# HEATER.net
KiCad netlist of a schematic drawn in Altium Designer
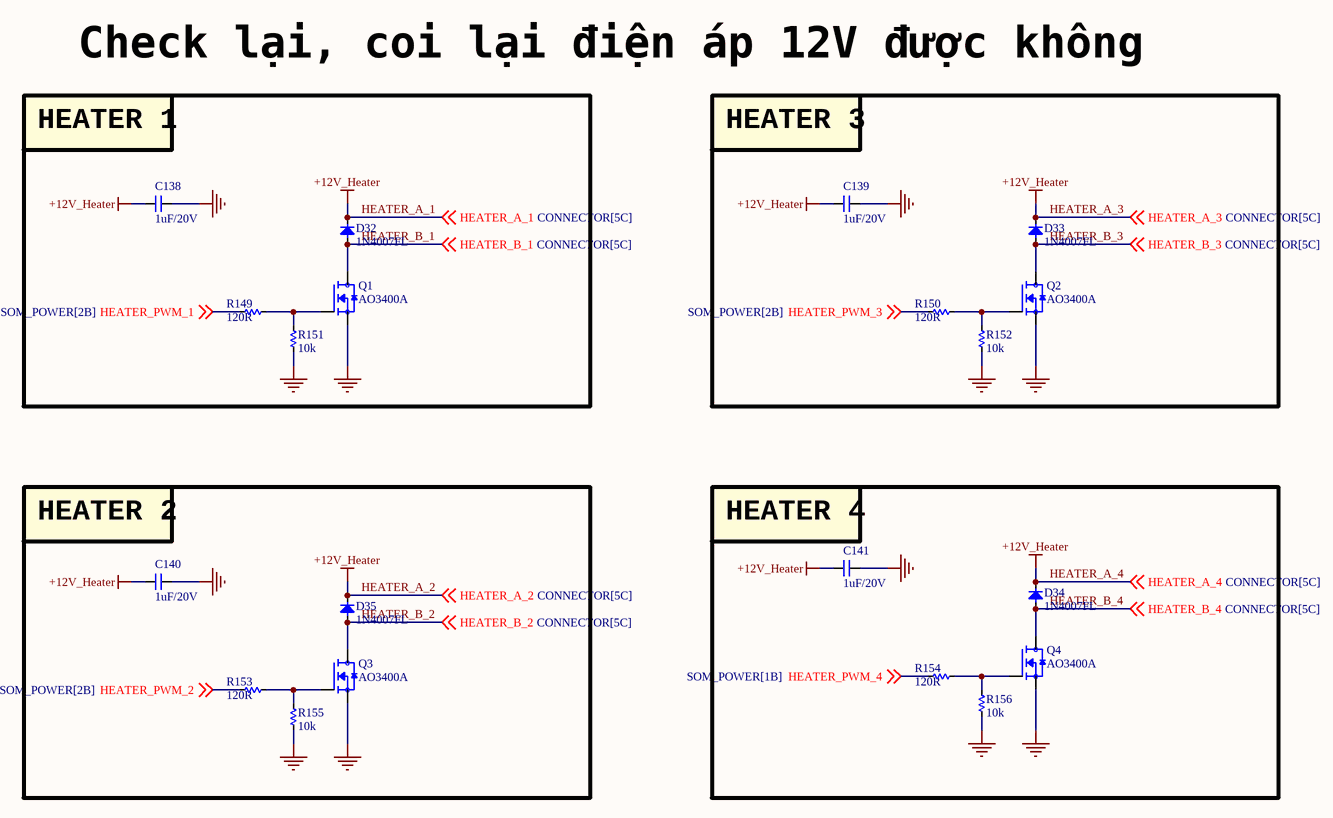
[diagram p0: HEATER.SchDoc]

(export (version "E")
  (design (tool "Eeschema 10.0.6"))
  (components
    (comp (ref "C138")
      (value "1uF/20V")
      (footprint "CAP_C_1005X60")
      (description "CAP CHIP")
      (libsource (lib "LABLIB") (part "_CAP_C_2"))
    )
    (comp (ref "C139")
      (value "1uF/20V")
      (footprint "CAP_C_1005X60")
      (description "CAP CHIP")
      (libsource (lib "LABLIB") (part "_CAP_C_2"))
    )
    (comp (ref "C140")
      (value "1uF/20V")
      (footprint "CAP_C_1005X60")
      (description "CAP CHIP")
      (libsource (lib "LABLIB") (part "_CAP_C_2"))
    )
    (comp (ref "C141")
      (value "1uF/20V")
      (footprint "CAP_C_1005X60")
      (description "CAP CHIP")
      (libsource (lib "LABLIB") (part "_CAP_C_2"))
    )
    (comp (ref "D32")
      (value "1N4007FL")
      (footprint "DIO-SMD-106")
      (description "Default Diode")
      (fields (field (name "PUBLISHER") "Altium Limited"))
      (libsource (lib "LABLIB") (part "Diode SMD"))
    )
    (comp (ref "D33")
      (value "1N4007FL")
      (footprint "DIO-SMD-106")
      (description "Default Diode")
      (fields (field (name "PUBLISHER") "Altium Limited"))
      (libsource (lib "LABLIB") (part "Diode SMD"))
    )
    (comp (ref "D34")
      (value "1N4007FL")
      (footprint "DIO-SMD-106")
      (description "Default Diode")
      (fields (field (name "PUBLISHER") "Altium Limited"))
      (libsource (lib "LABLIB") (part "Diode SMD"))
    )
    (comp (ref "D35")
      (value "1N4007FL")
      (footprint "DIO-SMD-106")
      (description "Default Diode")
      (fields (field (name "PUBLISHER") "Altium Limited"))
      (libsource (lib "LABLIB") (part "Diode SMD"))
    )
    (comp (ref "Q1")
      (value "AO3400A")
      (footprint "SOT95P240X120-3N")
      (description "N-Channel 30 V 5.7A (Ta) 1.4W (Ta) Surface Mount SOT-23-3")
      (fields (field (name "MF") "Alpha & Omega Semiconductor"))
      (libsource (lib "new_component") (part "MOSFET_N"))
    )
    (comp (ref "Q2")
      (value "AO3400A")
      (footprint "SOT95P240X120-3N")
      (description "N-Channel 30 V 5.7A (Ta) 1.4W (Ta) Surface Mount SOT-23-3")
      (fields (field (name "MF") "Alpha & Omega Semiconductor"))
      (libsource (lib "new_component") (part "MOSFET_N"))
    )
    (comp (ref "Q3")
      (value "AO3400A")
      (footprint "SOT95P240X120-3N")
      (description "N-Channel 30 V 5.7A (Ta) 1.4W (Ta) Surface Mount SOT-23-3")
      (fields (field (name "MF") "Alpha & Omega Semiconductor"))
      (libsource (lib "new_component") (part "MOSFET_N"))
    )
    (comp (ref "Q4")
      (value "AO3400A")
      (footprint "SOT95P240X120-3N")
      (description "N-Channel 30 V 5.7A (Ta) 1.4W (Ta) Surface Mount SOT-23-3")
      (fields (field (name "MF") "Alpha & Omega Semiconductor"))
      (libsource (lib "new_component") (part "MOSFET_N"))
    )
    (comp (ref "R149")
      (value "120R")
      (footprint "RES_C_1005X40")
      (description "RES")
      (libsource (lib "LABLIB") (part "_RES_B_2"))
    )
    (comp (ref "R150")
      (value "120R")
      (footprint "RES_C_1005X40")
      (description "RES")
      (libsource (lib "LABLIB") (part "_RES_B_2"))
    )
    (comp (ref "R151")
      (value "10k")
      (footprint "RES_C_1005X40")
      (description "RES")
      (libsource (lib "LABLIB") (part "_RES_B_2"))
    )
    (comp (ref "R152")
      (value "10k")
      (footprint "RES_C_1005X40")
      (description "RES")
      (libsource (lib "LABLIB") (part "_RES_B_2"))
    )
    (comp (ref "R153")
      (value "120R")
      (footprint "RES_C_1005X40")
      (description "RES")
      (libsource (lib "LABLIB") (part "_RES_B_2"))
    )
    (comp (ref "R154")
      (value "120R")
      (footprint "RES_C_1005X40")
      (description "RES")
      (libsource (lib "LABLIB") (part "_RES_B_2"))
    )
    (comp (ref "R155")
      (value "10k")
      (footprint "RES_C_1005X40")
      (description "RES")
      (libsource (lib "LABLIB") (part "_RES_B_2"))
    )
    (comp (ref "R156")
      (value "10k")
      (footprint "RES_C_1005X40")
      (description "RES")
      (libsource (lib "LABLIB") (part "_RES_B_2"))
    )
  )
  (nets
    (net (code "1") (name "+12V_Heater") (class "Default")
      (node (ref "C138") (pin "2") (pinfunction "2_2") (pintype "passive"))
      (node (ref "C139") (pin "2") (pinfunction "2_2") (pintype "passive"))
      (node (ref "C140") (pin "2") (pinfunction "2_2") (pintype "passive"))
      (node (ref "C141") (pin "2") (pinfunction "2_2") (pintype "passive"))
      (node (ref "D32") (pin "1") (pinfunction "K_1") (pintype "passive"))
      (node (ref "D33") (pin "1") (pinfunction "K_1") (pintype "passive"))
      (node (ref "D34") (pin "1") (pinfunction "K_1") (pintype "passive"))
      (node (ref "D35") (pin "1") (pinfunction "K_1") (pintype "passive"))
    )
    (net (code "2") (name "GND") (class "Default")
      (node (ref "C138") (pin "1") (pinfunction "1_1") (pintype "passive"))
      (node (ref "C139") (pin "1") (pinfunction "1_1") (pintype "passive"))
      (node (ref "C140") (pin "1") (pinfunction "1_1") (pintype "passive"))
      (node (ref "C141") (pin "1") (pinfunction "1_1") (pintype "passive"))
      (node (ref "Q1") (pin "2") (pinfunction "S_2") (pintype "passive"))
      (node (ref "Q2") (pin "2") (pinfunction "S_2") (pintype "passive"))
      (node (ref "Q3") (pin "2") (pinfunction "S_2") (pintype "passive"))
      (node (ref "Q4") (pin "2") (pinfunction "S_2") (pintype "passive"))
      (node (ref "R151") (pin "1") (pinfunction "1_1") (pintype "passive"))
      (node (ref "R152") (pin "1") (pinfunction "1_1") (pintype "passive"))
      (node (ref "R155") (pin "1") (pinfunction "1_1") (pintype "passive"))
      (node (ref "R156") (pin "1") (pinfunction "1_1") (pintype "passive"))
    )
    (net (code "3") (name "HEATER_B_1") (class "Default")
      (node (ref "D32") (pin "2") (pinfunction "A_2") (pintype "passive"))
      (node (ref "Q1") (pin "3") (pinfunction "D_3") (pintype "passive"))
    )
    (net (code "4") (name "HEATER_B_2") (class "Default")
      (node (ref "D35") (pin "2") (pinfunction "A_2") (pintype "passive"))
      (node (ref "Q3") (pin "3") (pinfunction "D_3") (pintype "passive"))
    )
    (net (code "5") (name "HEATER_B_3") (class "Default")
      (node (ref "D33") (pin "2") (pinfunction "A_2") (pintype "passive"))
      (node (ref "Q2") (pin "3") (pinfunction "D_3") (pintype "passive"))
    )
    (net (code "6") (name "HEATER_B_4") (class "Default")
      (node (ref "D34") (pin "2") (pinfunction "A_2") (pintype "passive"))
      (node (ref "Q4") (pin "3") (pinfunction "D_3") (pintype "passive"))
    )
    (net (code "7") (name "HEATER_PWM_1") (class "Default")
      (node (ref "R149") (pin "1") (pinfunction "1_1") (pintype "passive"))
    )
    (net (code "8") (name "HEATER_PWM_2") (class "Default")
      (node (ref "R153") (pin "1") (pinfunction "1_1") (pintype "passive"))
    )
    (net (code "9") (name "HEATER_PWM_3") (class "Default")
      (node (ref "R150") (pin "1") (pinfunction "1_1") (pintype "passive"))
    )
    (net (code "10") (name "HEATER_PWM_4") (class "Default")
      (node (ref "R154") (pin "1") (pinfunction "1_1") (pintype "passive"))
    )
    (net (code "11") (name "Net-(Q1-G)") (class "Default")
      (node (ref "Q1") (pin "1") (pinfunction "G_1") (pintype "passive"))
      (node (ref "R149") (pin "2") (pinfunction "2_2") (pintype "passive"))
      (node (ref "R151") (pin "2") (pinfunction "2_2") (pintype "passive"))
    )
    (net (code "12") (name "Net-(Q2-G)") (class "Default")
      (node (ref "Q2") (pin "1") (pinfunction "G_1") (pintype "passive"))
      (node (ref "R150") (pin "2") (pinfunction "2_2") (pintype "passive"))
      (node (ref "R152") (pin "2") (pinfunction "2_2") (pintype "passive"))
    )
    (net (code "13") (name "Net-(Q3-G)") (class "Default")
      (node (ref "Q3") (pin "1") (pinfunction "G_1") (pintype "passive"))
      (node (ref "R153") (pin "2") (pinfunction "2_2") (pintype "passive"))
      (node (ref "R155") (pin "2") (pinfunction "2_2") (pintype "passive"))
    )
    (net (code "14") (name "Net-(Q4-G)") (class "Default")
      (node (ref "Q4") (pin "1") (pinfunction "G_1") (pintype "passive"))
      (node (ref "R154") (pin "2") (pinfunction "2_2") (pintype "passive"))
      (node (ref "R156") (pin "2") (pinfunction "2_2") (pintype "passive"))
    )
  )
)
